# master-board.net
KiCad netlist of a schematic drawn in EAGLE
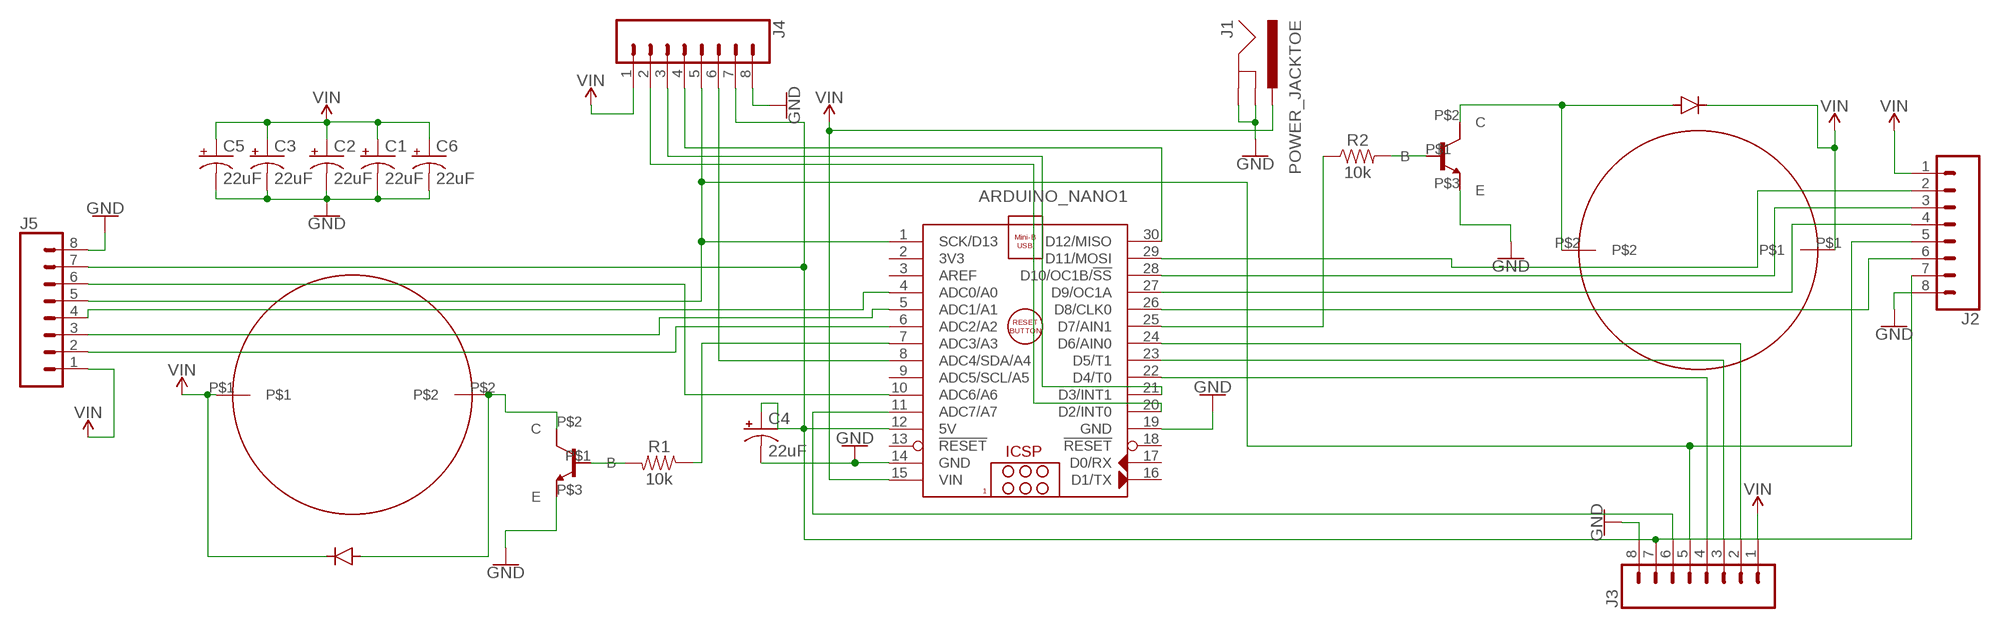
[diagram p0: schematic, sheet 1]

(export (version "E")
  (design (tool "Eeschema 10.0.6"))
  (components
    (comp (ref "ARDUINO_NANO1")
      (value "ARDUINO_NANO")
      (footprint "eagle-import:ARDUINO_NANO")
      (libsource (lib "eagle-import") (part "ARDUINO_NANO"))
    )
    (comp (ref "C1")
      (value "22uF")
      (footprint "eagle-import:PANASONIC_C")
      (libsource (lib "eagle-import") (part "22UF-POLAR-PANASONIC_C-35V-20%"))
    )
    (comp (ref "C2")
      (value "22uF")
      (footprint "eagle-import:PANASONIC_C")
      (libsource (lib "eagle-import") (part "22UF-POLAR-PANASONIC_C-35V-20%"))
    )
    (comp (ref "C3")
      (value "22uF")
      (footprint "eagle-import:PANASONIC_C")
      (libsource (lib "eagle-import") (part "22UF-POLAR-PANASONIC_C-35V-20%"))
    )
    (comp (ref "C4")
      (value "22uF")
      (footprint "eagle-import:PANASONIC_C")
      (libsource (lib "eagle-import") (part "22UF-POLAR-PANASONIC_C-35V-20%"))
    )
    (comp (ref "C5")
      (value "22uF")
      (footprint "eagle-import:PANASONIC_C")
      (libsource (lib "eagle-import") (part "22UF-POLAR-PANASONIC_C-35V-20%"))
    )
    (comp (ref "C6")
      (value "22uF")
      (footprint "eagle-import:PANASONIC_C")
      (libsource (lib "eagle-import") (part "22UF-POLAR-PANASONIC_C-35V-20%"))
    )
    (comp (ref "J1")
      (value "POWER_JACKTOE")
      (footprint "eagle-import:POWER_JACK_SMD_OVERPASTE_TOE")
      (libsource (lib "eagle-import") (part "POWER_JACKTOE"))
    )
    (comp (ref "J2")
      (value "CONN_08\"")
      (footprint "eagle-import:1X08")
      (libsource (lib "eagle-import") (part "CONN_08{dblquote}"))
    )
    (comp (ref "J3")
      (value "CONN_08\"")
      (footprint "eagle-import:1X08")
      (libsource (lib "eagle-import") (part "CONN_08{dblquote}"))
    )
    (comp (ref "J4")
      (value "CONN_08\"")
      (footprint "eagle-import:1X08")
      (libsource (lib "eagle-import") (part "CONN_08{dblquote}"))
    )
    (comp (ref "J5")
      (value "CONN_08\"")
      (footprint "eagle-import:1X08")
      (libsource (lib "eagle-import") (part "CONN_08{dblquote}"))
    )
    (comp (ref "R1")
      (value "10k")
      (footprint "eagle-import:0603")
      (libsource (lib "eagle-import") (part "10KOHM-0603-1/10W-1%"))
    )
    (comp (ref "R2")
      (value "10k")
      (footprint "eagle-import:0603")
      (libsource (lib "eagle-import") (part "10KOHM-0603-1/10W-1%"))
    )
    (comp (ref "U$1")
      (value "AIYIMA-PUMP-A5F083")
      (footprint "eagle-import:A5F083")
      (libsource (lib "eagle-import") (part "AIYIMA-PUMP-A5F083"))
    )
    (comp (ref "U$2")
      (value "AIYIMA-PUMP-A5F083")
      (footprint "eagle-import:A5F083")
      (libsource (lib "eagle-import") (part "AIYIMA-PUMP-A5F083"))
    )
    (comp (ref "U$3")
      (value "IN4148")
      (footprint "eagle-import:IN4148")
      (libsource (lib "eagle-import") (part "IN4148"))
    )
    (comp (ref "U$4")
      (value "IN4148")
      (footprint "eagle-import:IN4148")
      (libsource (lib "eagle-import") (part "IN4148"))
    )
    (comp (ref "U$5")
      (value "TIP120-TO220")
      (footprint "eagle-import:TO220")
      (libsource (lib "eagle-import") (part "TIP120-TO220"))
    )
    (comp (ref "U$6")
      (value "TIP120-TO220")
      (footprint "eagle-import:TO220")
      (libsource (lib "eagle-import") (part "TIP120-TO220"))
    )
  )
  (nets
    (net (code "1") (name "GND") (class "Default")
      (node (ref "ARDUINO_NANO1") (pin "14") (pinfunction "GND_14") (pintype "power_in"))
      (node (ref "ARDUINO_NANO1") (pin "19") (pinfunction "GND_19") (pintype "power_in"))
      (node (ref "C1") (pin "-") (pinfunction "-_-") (pintype "passive"))
      (node (ref "C2") (pin "-") (pinfunction "-_-") (pintype "passive"))
      (node (ref "C3") (pin "-") (pinfunction "-_-") (pintype "passive"))
      (node (ref "C4") (pin "-") (pinfunction "-_-") (pintype "passive"))
      (node (ref "C5") (pin "-") (pinfunction "-_-") (pintype "passive"))
      (node (ref "C6") (pin "-") (pinfunction "-_-") (pintype "passive"))
      (node (ref "J1") (pin "GND") (pinfunction "GNDBREAK_GND") (pintype "bidirectional"))
      (node (ref "J1") (pin "P$4") (pinfunction "GND_P$4") (pintype "bidirectional"))
      (node (ref "J2") (pin "8") (pinfunction "8_8") (pintype "passive"))
      (node (ref "J3") (pin "8") (pinfunction "8_8") (pintype "passive"))
      (node (ref "J4") (pin "8") (pinfunction "8_8") (pintype "passive"))
      (node (ref "J5") (pin "8") (pinfunction "8_8") (pintype "passive"))
      (node (ref "U$5") (pin "P$3") (pinfunction "E_P$3") (pintype "bidirectional"))
      (node (ref "U$6") (pin "P$3") (pinfunction "E_P$3") (pintype "bidirectional"))
    )
    (net (code "2") (name "Net-(ARDUINO_NANO1-5V)") (class "Default")
      (node (ref "ARDUINO_NANO1") (pin "12") (pinfunction "5V_12") (pintype "power_in"))
      (node (ref "C4") (pin "+") (pinfunction "+_+") (pintype "passive"))
      (node (ref "J2") (pin "7") (pinfunction "7_7") (pintype "passive"))
      (node (ref "J3") (pin "7") (pinfunction "7_7") (pintype "passive"))
      (node (ref "J4") (pin "7") (pinfunction "7_7") (pintype "passive"))
      (node (ref "J5") (pin "7") (pinfunction "7_7") (pintype "passive"))
    )
    (net (code "3") (name "Net-(ARDUINO_NANO1-ADC0{slash}A0)") (class "Default")
      (node (ref "ARDUINO_NANO1") (pin "4") (pinfunction "ADC0/A0_4") (pintype "bidirectional"))
      (node (ref "J5") (pin "4") (pinfunction "4_4") (pintype "passive"))
    )
    (net (code "4") (name "Net-(ARDUINO_NANO1-ADC1{slash}A1)") (class "Default")
      (node (ref "ARDUINO_NANO1") (pin "5") (pinfunction "ADC1/A1_5") (pintype "bidirectional"))
      (node (ref "J5") (pin "3") (pinfunction "3_3") (pintype "passive"))
    )
    (net (code "5") (name "Net-(ARDUINO_NANO1-ADC2{slash}A2)") (class "Default")
      (node (ref "ARDUINO_NANO1") (pin "6") (pinfunction "ADC2/A2_6") (pintype "bidirectional"))
      (node (ref "J5") (pin "2") (pinfunction "2_2") (pintype "passive"))
    )
    (net (code "6") (name "Net-(ARDUINO_NANO1-ADC3{slash}A3)") (class "Default")
      (node (ref "ARDUINO_NANO1") (pin "7") (pinfunction "ADC3/A3_7") (pintype "bidirectional"))
      (node (ref "R1") (pin "1") (pinfunction "1_1") (pintype "passive"))
    )
    (net (code "7") (name "Net-(ARDUINO_NANO1-ADC4{slash}SDA{slash}A4)") (class "Default")
      (node (ref "ARDUINO_NANO1") (pin "8") (pinfunction "ADC4/SDA/A4_8") (pintype "bidirectional"))
      (node (ref "J4") (pin "6") (pinfunction "6_6") (pintype "passive"))
    )
    (net (code "8") (name "Net-(ARDUINO_NANO1-ADC6{slash}A6)") (class "Default")
      (node (ref "ARDUINO_NANO1") (pin "10") (pinfunction "ADC6/A6_10") (pintype "bidirectional"))
      (node (ref "J5") (pin "6") (pinfunction "6_6") (pintype "passive"))
    )
    (net (code "9") (name "Net-(ARDUINO_NANO1-ADC7{slash}A7)") (class "Default")
      (node (ref "ARDUINO_NANO1") (pin "11") (pinfunction "ADC7/A7_11") (pintype "bidirectional"))
      (node (ref "J3") (pin "6") (pinfunction "6_6") (pintype "passive"))
    )
    (net (code "10") (name "Net-(ARDUINO_NANO1-D2{slash}INT0)") (class "Default")
      (node (ref "ARDUINO_NANO1") (pin "20") (pinfunction "D2/INT0_20") (pintype "bidirectional"))
      (node (ref "J4") (pin "2") (pinfunction "2_2") (pintype "passive"))
    )
    (net (code "11") (name "Net-(ARDUINO_NANO1-D3{slash}INT1)") (class "Default")
      (node (ref "ARDUINO_NANO1") (pin "21") (pinfunction "D3/INT1_21") (pintype "bidirectional"))
      (node (ref "J4") (pin "3") (pinfunction "3_3") (pintype "passive"))
    )
    (net (code "12") (name "Net-(ARDUINO_NANO1-D4{slash}T0)") (class "Default")
      (node (ref "ARDUINO_NANO1") (pin "22") (pinfunction "D4/T0_22") (pintype "bidirectional"))
      (node (ref "J3") (pin "4") (pinfunction "4_4") (pintype "passive"))
    )
    (net (code "13") (name "Net-(ARDUINO_NANO1-D5{slash}T1)") (class "Default")
      (node (ref "ARDUINO_NANO1") (pin "23") (pinfunction "D5/T1_23") (pintype "bidirectional"))
      (node (ref "J3") (pin "3") (pinfunction "3_3") (pintype "passive"))
    )
    (net (code "14") (name "Net-(ARDUINO_NANO1-D6{slash}AIN0)") (class "Default")
      (node (ref "ARDUINO_NANO1") (pin "24") (pinfunction "D6/AIN0_24") (pintype "bidirectional"))
      (node (ref "J3") (pin "2") (pinfunction "2_2") (pintype "passive"))
    )
    (net (code "15") (name "Net-(ARDUINO_NANO1-D7{slash}AIN1)") (class "Default")
      (node (ref "ARDUINO_NANO1") (pin "25") (pinfunction "D7/AIN1_25") (pintype "bidirectional"))
      (node (ref "R2") (pin "1") (pinfunction "1_1") (pintype "passive"))
    )
    (net (code "16") (name "Net-(ARDUINO_NANO1-D8{slash}CLK0)") (class "Default")
      (node (ref "ARDUINO_NANO1") (pin "26") (pinfunction "D8/CLK0_26") (pintype "bidirectional"))
      (node (ref "J2") (pin "6") (pinfunction "6_6") (pintype "passive"))
    )
    (net (code "17") (name "Net-(ARDUINO_NANO1-D9{slash}OC1A)") (class "Default")
      (node (ref "ARDUINO_NANO1") (pin "27") (pinfunction "D9/OC1A_27") (pintype "bidirectional"))
      (node (ref "J2") (pin "4") (pinfunction "4_4") (pintype "passive"))
    )
    (net (code "18") (name "Net-(ARDUINO_NANO1-D10{slash}OC1B{slash}~{SS})") (class "Default")
      (node (ref "ARDUINO_NANO1") (pin "28") (pinfunction "D10/OC1B/~{SS}_28") (pintype "bidirectional"))
      (node (ref "J2") (pin "3") (pinfunction "3_3") (pintype "passive"))
    )
    (net (code "19") (name "Net-(ARDUINO_NANO1-D11{slash}MOSI)") (class "Default")
      (node (ref "ARDUINO_NANO1") (pin "29") (pinfunction "D11/MOSI_29") (pintype "bidirectional"))
      (node (ref "J2") (pin "2") (pinfunction "2_2") (pintype "passive"))
    )
    (net (code "20") (name "Net-(ARDUINO_NANO1-D12{slash}MISO)") (class "Default")
      (node (ref "ARDUINO_NANO1") (pin "30") (pinfunction "D12/MISO_30") (pintype "bidirectional"))
      (node (ref "J4") (pin "4") (pinfunction "4_4") (pintype "passive"))
    )
    (net (code "21") (name "Net-(ARDUINO_NANO1-SCK{slash}D13)") (class "Default")
      (node (ref "ARDUINO_NANO1") (pin "1") (pinfunction "SCK/D13_1") (pintype "bidirectional"))
      (node (ref "J2") (pin "5") (pinfunction "5_5") (pintype "passive"))
      (node (ref "J3") (pin "5") (pinfunction "5_5") (pintype "passive"))
      (node (ref "J4") (pin "5") (pinfunction "5_5") (pintype "passive"))
      (node (ref "J5") (pin "5") (pinfunction "5_5") (pintype "passive"))
    )
    (net (code "22") (name "Net-(U$5-B)") (class "Default")
      (node (ref "R2") (pin "2") (pinfunction "2_2") (pintype "passive"))
      (node (ref "U$5") (pin "P$1") (pinfunction "B_P$1") (pintype "bidirectional"))
    )
    (net (code "23") (name "Net-(U$5-C)") (class "Default")
      (node (ref "U$2") (pin "P$2") (pinfunction "P$2_P$2") (pintype "bidirectional"))
      (node (ref "U$4") (pin "P$2") (pinfunction "P$2_P$2") (pintype "bidirectional"))
      (node (ref "U$5") (pin "P$2") (pinfunction "C_P$2") (pintype "bidirectional"))
    )
    (net (code "24") (name "Net-(U$6-B)") (class "Default")
      (node (ref "R1") (pin "2") (pinfunction "2_2") (pintype "passive"))
      (node (ref "U$6") (pin "P$1") (pinfunction "B_P$1") (pintype "bidirectional"))
    )
    (net (code "25") (name "Net-(U$6-C)") (class "Default")
      (node (ref "U$1") (pin "P$2") (pinfunction "P$2_P$2") (pintype "bidirectional"))
      (node (ref "U$3") (pin "P$2") (pinfunction "P$2_P$2") (pintype "bidirectional"))
      (node (ref "U$6") (pin "P$2") (pinfunction "C_P$2") (pintype "bidirectional"))
    )
    (net (code "26") (name "VIN") (class "Default")
      (node (ref "ARDUINO_NANO1") (pin "15") (pinfunction "VIN_15") (pintype "power_in"))
      (node (ref "C1") (pin "+") (pinfunction "+_+") (pintype "passive"))
      (node (ref "C2") (pin "+") (pinfunction "+_+") (pintype "passive"))
      (node (ref "C3") (pin "+") (pinfunction "+_+") (pintype "passive"))
      (node (ref "C5") (pin "+") (pinfunction "+_+") (pintype "passive"))
      (node (ref "C6") (pin "+") (pinfunction "+_+") (pintype "passive"))
      (node (ref "J1") (pin "VIN0") (pinfunction "PWR_VIN0") (pintype "bidirectional"))
      (node (ref "J2") (pin "1") (pinfunction "1_1") (pintype "passive"))
      (node (ref "J3") (pin "1") (pinfunction "1_1") (pintype "passive"))
      (node (ref "J4") (pin "1") (pinfunction "1_1") (pintype "passive"))
      (node (ref "J5") (pin "1") (pinfunction "1_1") (pintype "passive"))
      (node (ref "U$1") (pin "P$1") (pinfunction "P$1_P$1") (pintype "bidirectional"))
      (node (ref "U$2") (pin "P$1") (pinfunction "P$1_P$1") (pintype "bidirectional"))
      (node (ref "U$3") (pin "P$1") (pinfunction "P$1_P$1") (pintype "bidirectional"))
      (node (ref "U$4") (pin "P$1") (pinfunction "P$1_P$1") (pintype "bidirectional"))
    )
    (net (code "27") (name "unconnected-(ARDUINO_NANO1-3V3-Pad2)") (class "Default")
      (node (ref "ARDUINO_NANO1") (pin "2") (pinfunction "3V3_2") (pintype "output"))
    )
    (net (code "28") (name "unconnected-(ARDUINO_NANO1-ADC5{slash}SCL{slash}A5-Pad9)") (class "Default")
      (node (ref "ARDUINO_NANO1") (pin "9") (pinfunction "ADC5/SCL/A5_9") (pintype "bidirectional"))
    )
    (net (code "29") (name "unconnected-(ARDUINO_NANO1-AREF-Pad3)") (class "Default")
      (node (ref "ARDUINO_NANO1") (pin "3") (pinfunction "AREF_3") (pintype "input"))
    )
    (net (code "30") (name "unconnected-(ARDUINO_NANO1-D0{slash}RX-Pad17)") (class "Default")
      (node (ref "ARDUINO_NANO1") (pin "17") (pinfunction "D0/RX_17") (pintype "bidirectional"))
    )
    (net (code "31") (name "unconnected-(ARDUINO_NANO1-D1{slash}TX-Pad16)") (class "Default")
      (node (ref "ARDUINO_NANO1") (pin "16") (pinfunction "D1/TX_16") (pintype "bidirectional"))
    )
    (net (code "32") (name "unconnected-(ARDUINO_NANO1-~{RESET}-Pad13)") (class "Default")
      (node (ref "ARDUINO_NANO1") (pin "13") (pinfunction "~{RESET}_13") (pintype "input"))
    )
    (net (code "33") (name "unconnected-(ARDUINO_NANO1-~{RESET}-Pad18)") (class "Default")
      (node (ref "ARDUINO_NANO1") (pin "18") (pinfunction "~{RESET}_18") (pintype "input"))
    )
  )
)
